# main.net
KiCad netlist of a schematic drawn in EAGLE
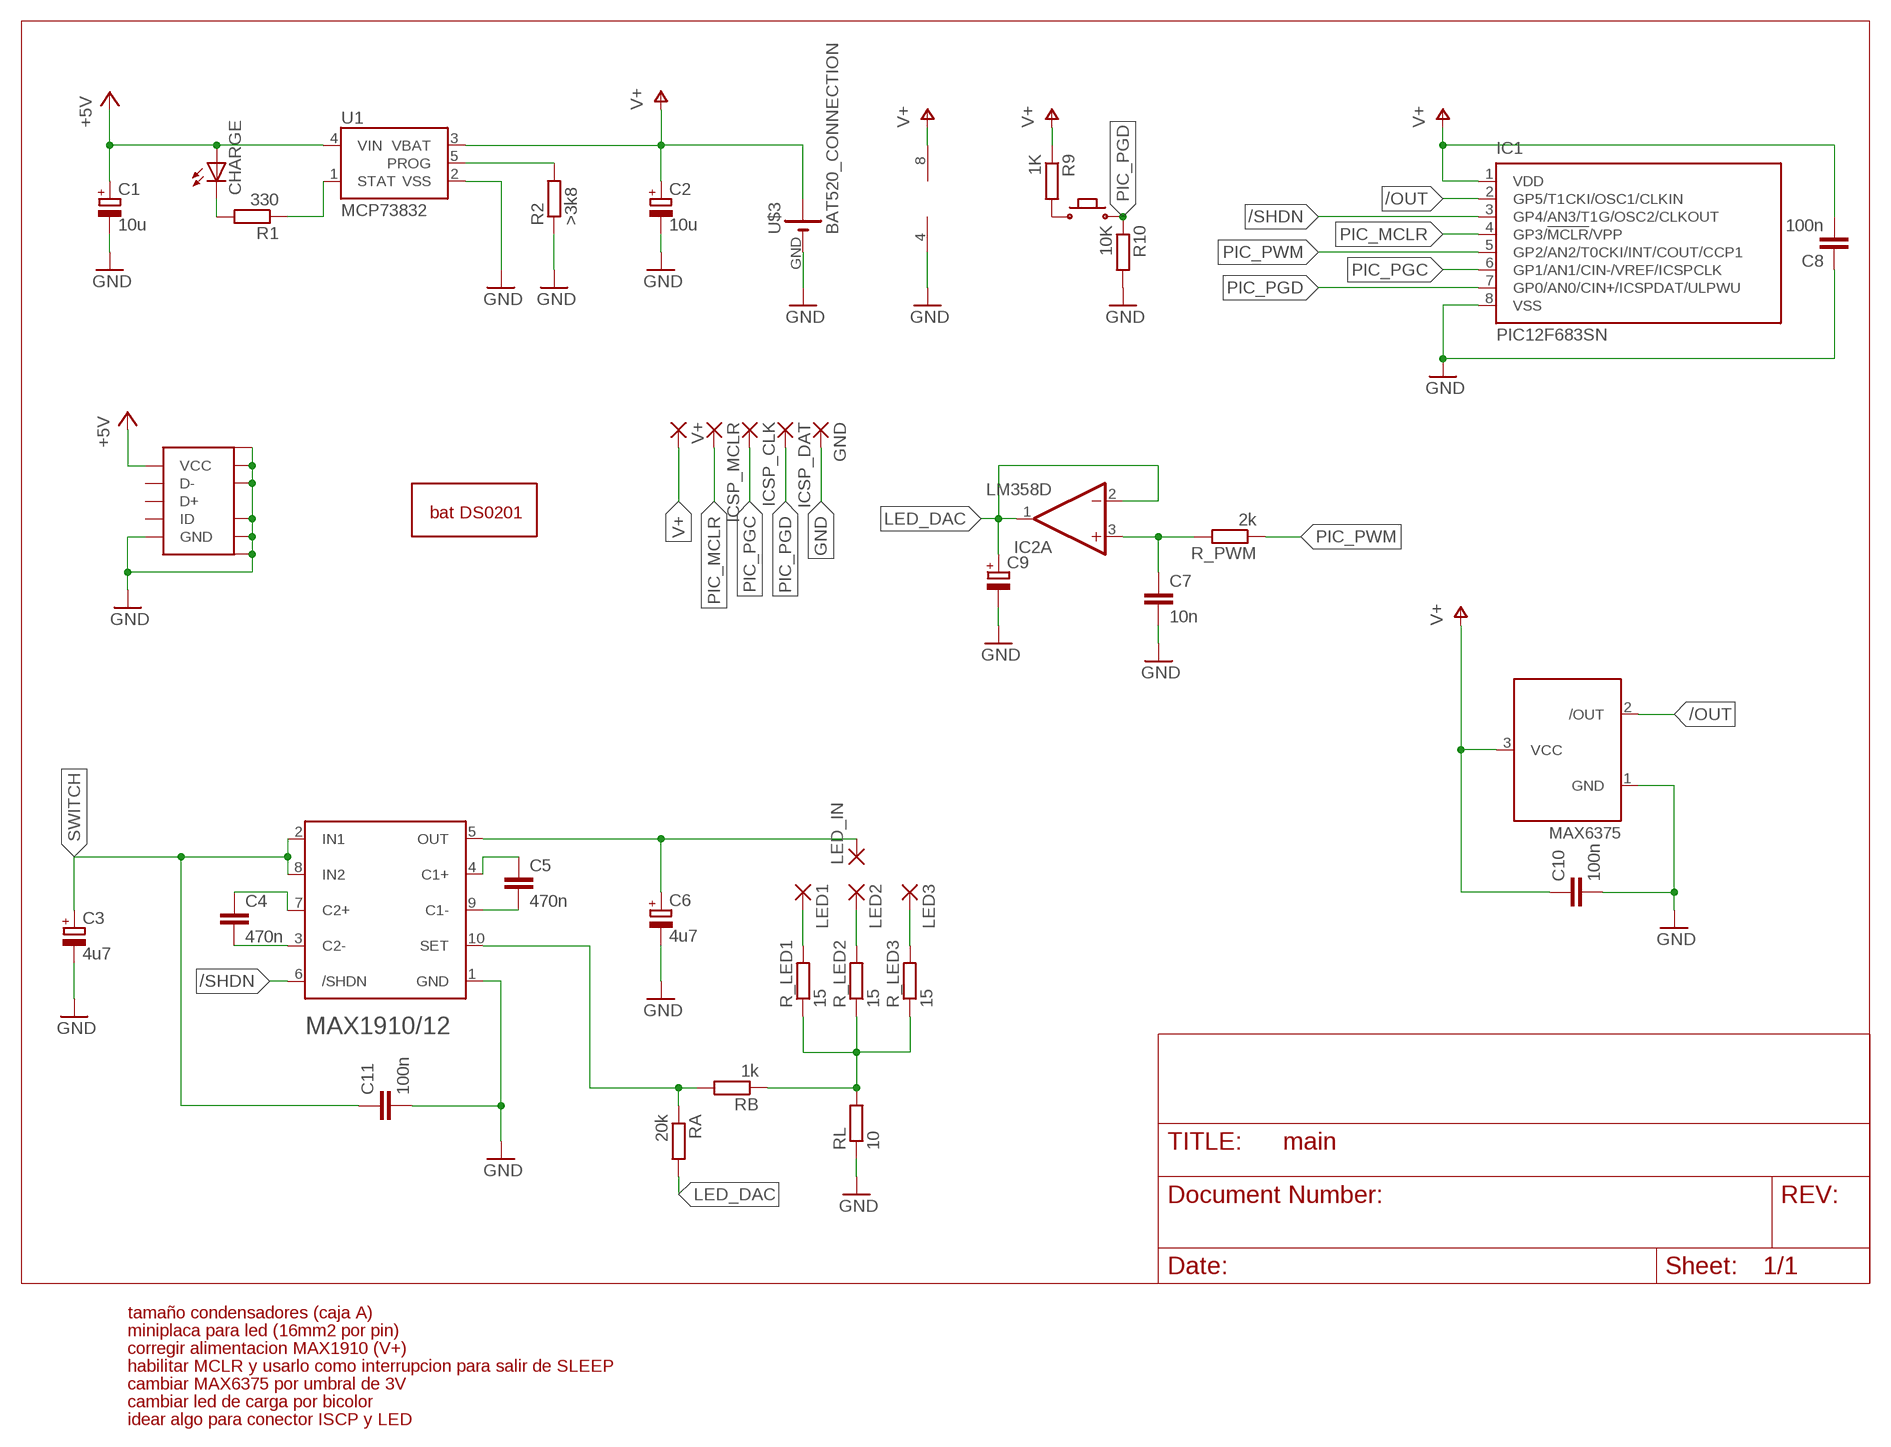
[diagram p0: schematic, sheet 1]

(export (version "E")
  (design (tool "Eeschema 10.0.6"))
  (components
    (comp (ref "C1")
      (value "10u")
      (footprint "eagle-import:SMC_A")
      (libsource (lib "eagle-import") (part "CPOL-EUSMCA"))
    )
    (comp (ref "C2")
      (value "10u")
      (footprint "eagle-import:SMC_A")
      (libsource (lib "eagle-import") (part "CPOL-EUSMCA"))
    )
    (comp (ref "C3")
      (value "4u7")
      (footprint "eagle-import:SMC_A")
      (libsource (lib "eagle-import") (part "CPOL-EUSMCA"))
    )
    (comp (ref "C4")
      (value "470n")
      (footprint "eagle-import:C1206")
      (libsource (lib "eagle-import") (part "C-EUC1206"))
    )
    (comp (ref "C5")
      (value "470n")
      (footprint "eagle-import:C1206")
      (libsource (lib "eagle-import") (part "C-EUC1206"))
    )
    (comp (ref "C6")
      (value "4u7")
      (footprint "eagle-import:SMC_A")
      (libsource (lib "eagle-import") (part "CPOL-EUSMCA"))
    )
    (comp (ref "C7")
      (value "10n")
      (footprint "eagle-import:C1206")
      (libsource (lib "eagle-import") (part "C-EUC1206"))
    )
    (comp (ref "C8")
      (value "100n")
      (footprint "eagle-import:C1206")
      (libsource (lib "eagle-import") (part "C-EUC1206"))
    )
    (comp (ref "C9")
      (value "CPOL-EUSMCA")
      (footprint "eagle-import:SMC_A")
      (libsource (lib "eagle-import") (part "CPOL-EUSMCA"))
    )
    (comp (ref "C10")
      (value "100n")
      (footprint "eagle-import:C1206")
      (libsource (lib "eagle-import") (part "C-EUC1206"))
    )
    (comp (ref "C11")
      (value "100n")
      (footprint "eagle-import:C1206")
      (libsource (lib "eagle-import") (part "C-EUC1206"))
    )
    (comp (ref "CHARGE")
      (value "LEDCHIPLED_1206")
      (footprint "eagle-import:CHIPLED_1206")
      (libsource (lib "eagle-import") (part "LEDCHIPLED_1206"))
    )
    (comp (ref "GND")
      (value "SMD5")
      (footprint "eagle-import:SMD2,54-5,08")
      (libsource (lib "eagle-import") (part "SMD5"))
    )
    (comp (ref "IC1")
      (value "PIC12F683SN")
      (footprint "eagle-import:SO-08")
      (fields (field (name "MF") "MICROCHIP") (field (name "MPN") "PIC12F683-I/SN"))
      (libsource (lib "eagle-import") (part "PIC12F683SN"))
    )
    (comp (ref "IC2")
      (value "LM358D")
      (footprint "eagle-import:SO08")
      (libsource (lib "eagle-import") (part "LM358D"))
    )
    (comp (ref "ICSP_CLK")
      (value "SMD5")
      (footprint "eagle-import:SMD2,54-5,08")
      (libsource (lib "eagle-import") (part "SMD5"))
    )
    (comp (ref "ICSP_DAT")
      (value "SMD5")
      (footprint "eagle-import:SMD2,54-5,08")
      (libsource (lib "eagle-import") (part "SMD5"))
    )
    (comp (ref "ICSP_MCLR")
      (value "SMD5")
      (footprint "eagle-import:SMD2,54-5,08")
      (libsource (lib "eagle-import") (part "SMD5"))
    )
    (comp (ref "LED1")
      (value "SMD5")
      (footprint "eagle-import:SMD2,54-5,08")
      (libsource (lib "eagle-import") (part "SMD5"))
    )
    (comp (ref "LED2")
      (value "SMD5")
      (footprint "eagle-import:SMD2,54-5,08")
      (libsource (lib "eagle-import") (part "SMD5"))
    )
    (comp (ref "LED3")
      (value "SMD5")
      (footprint "eagle-import:SMD2,54-5,08")
      (libsource (lib "eagle-import") (part "SMD5"))
    )
    (comp (ref "LED_IN")
      (value "SMD5")
      (footprint "eagle-import:SMD2,54-5,08")
      (libsource (lib "eagle-import") (part "SMD5"))
    )
    (comp (ref "R1")
      (value "330")
      (footprint "eagle-import:R1206")
      (libsource (lib "eagle-import") (part "R-EU_R1206"))
    )
    (comp (ref "R2")
      (value ">3k8")
      (footprint "eagle-import:R1206")
      (libsource (lib "eagle-import") (part "R-EU_R1206"))
    )
    (comp (ref "R9")
      (value "1K")
      (footprint "eagle-import:R1206")
      (libsource (lib "eagle-import") (part "R-EU_R1206"))
    )
    (comp (ref "R10")
      (value "10K")
      (footprint "eagle-import:R1206")
      (libsource (lib "eagle-import") (part "R-EU_R1206"))
    )
    (comp (ref "RA")
      (value "20k")
      (footprint "eagle-import:R1206")
      (libsource (lib "eagle-import") (part "R-EU_R1206"))
    )
    (comp (ref "RB")
      (value "1k")
      (footprint "eagle-import:R1206")
      (libsource (lib "eagle-import") (part "R-EU_R1206"))
    )
    (comp (ref "RL")
      (value "10")
      (footprint "eagle-import:R1206")
      (libsource (lib "eagle-import") (part "R-EU_R1206"))
    )
    (comp (ref "R_LED1")
      (value "15")
      (footprint "eagle-import:R1206")
      (libsource (lib "eagle-import") (part "R-EU_R1206"))
    )
    (comp (ref "R_LED2")
      (value "15")
      (footprint "eagle-import:R1206")
      (libsource (lib "eagle-import") (part "R-EU_R1206"))
    )
    (comp (ref "R_LED3")
      (value "15")
      (footprint "eagle-import:R1206")
      (libsource (lib "eagle-import") (part "R-EU_R1206"))
    )
    (comp (ref "R_PWM")
      (value "2k")
      (footprint "eagle-import:R1206")
      (libsource (lib "eagle-import") (part "R-EU_R1206"))
    )
    (comp (ref "U$1")
      (value "MAX1910/12")
      (footprint "eagle-import:UMAX_USOP_10L")
      (libsource (lib "eagle-import") (part "MAX1910/12"))
    )
    (comp (ref "U$2")
      (value "MAX6375")
      (footprint "eagle-import:SC70-3-W")
      (libsource (lib "eagle-import") (part "MAX6375"))
    )
    (comp (ref "U$3")
      (value "BAT520_CONNECTION")
      (footprint "eagle-import:BAT520_CONN_SMD")
      (libsource (lib "eagle-import") (part "BAT520_CONNECTION"))
    )
    (comp (ref "U$4")
      (value "BAT_DS0201_PACKAGE")
      (footprint "eagle-import:BAT_DS0201")
      (libsource (lib "eagle-import") (part "BAT_DS0201_PACKAGE"))
    )
    (comp (ref "U$5")
      (value "MICRO_USB_B")
      (footprint "eagle-import:MICRO_USB_B")
      (libsource (lib "eagle-import") (part "MICRO_USB_B"))
    )
    (comp (ref "U$6")
      (value "MICROBUTTONE-MERCHAN")
      (footprint "eagle-import:MICROBUTTON_2")
      (libsource (lib "eagle-import") (part "MICROBUTTONE-MERCHAN"))
    )
    (comp (ref "U1")
      (value "MCP73832")
      (footprint "eagle-import:SOT23-5")
      (libsource (lib "eagle-import") (part "MCP73832"))
    )
    (comp (ref "V+")
      (value "SMD5")
      (footprint "eagle-import:SMD2,54-5,08")
      (libsource (lib "eagle-import") (part "SMD5"))
    )
  )
  (nets
    (net (code "1") (name "+5V") (class "Default")
      (node (ref "C1") (pin "+") (pinfunction "+_+") (pintype "passive"))
      (node (ref "CHARGE") (pin "A") (pinfunction "A_A") (pintype "passive"))
      (node (ref "U$5") (pin "1") (pinfunction "VCC_1") (pintype "power_in"))
      (node (ref "U1") (pin "4") (pinfunction "VIN_4") (pintype "power_in"))
    )
    (net (code "2") (name "GND") (class "Default")
      (node (ref "C1") (pin "-") (pinfunction "-_-") (pintype "passive"))
      (node (ref "C10") (pin "2") (pinfunction "2_2") (pintype "passive"))
      (node (ref "C11") (pin "2") (pinfunction "2_2") (pintype "passive"))
      (node (ref "C2") (pin "-") (pinfunction "-_-") (pintype "passive"))
      (node (ref "C3") (pin "-") (pinfunction "-_-") (pintype "passive"))
      (node (ref "C6") (pin "-") (pinfunction "-_-") (pintype "passive"))
      (node (ref "C7") (pin "2") (pinfunction "2_2") (pintype "passive"))
      (node (ref "C8") (pin "1") (pinfunction "1_1") (pintype "passive"))
      (node (ref "C9") (pin "-") (pinfunction "-_-") (pintype "passive"))
      (node (ref "GND") (pin "1") (pinfunction "P_1") (pintype "passive"))
      (node (ref "IC1") (pin "8") (pinfunction "VSS_8") (pintype "power_in"))
      (node (ref "IC2") (pin "4") (pinfunction "V-_4") (pintype "power_in"))
      (node (ref "R10") (pin "2") (pinfunction "2_2") (pintype "passive"))
      (node (ref "R2") (pin "1") (pinfunction "1_1") (pintype "passive"))
      (node (ref "RL") (pin "1") (pinfunction "1_1") (pintype "passive"))
      (node (ref "U$1") (pin "1") (pinfunction "GND_1") (pintype "power_in"))
      (node (ref "U$2") (pin "1") (pinfunction "GND_1") (pintype "power_in"))
      (node (ref "U$3") (pin "GND") (pinfunction "-_GND") (pintype "passive"))
      (node (ref "U$5") (pin "5") (pinfunction "GND_5") (pintype "power_in"))
      (node (ref "U$5") (pin "GND1") (pinfunction "GND_GND1") (pintype "power_in"))
      (node (ref "U$5") (pin "GND2") (pinfunction "GND_GND2") (pintype "power_in"))
      (node (ref "U$5") (pin "GND3") (pinfunction "GND_GND3") (pintype "power_in"))
      (node (ref "U$5") (pin "GND4") (pinfunction "GND_GND4") (pintype "power_in"))
      (node (ref "U$5") (pin "GND5") (pinfunction "GND_GND5") (pintype "power_in"))
      (node (ref "U$5") (pin "GND6") (pinfunction "GND_GND6") (pintype "power_in"))
      (node (ref "U1") (pin "2") (pinfunction "VSS_2") (pintype "power_in"))
    )
    (net (code "3") (name "LED_DAC") (class "Default")
      (node (ref "C9") (pin "+") (pinfunction "+_+") (pintype "passive"))
      (node (ref "IC2") (pin "1") (pinfunction "OUT_1") (pintype "output"))
      (node (ref "IC2") (pin "2") (pinfunction "-IN_2") (pintype "input"))
      (node (ref "RA") (pin "2") (pinfunction "2_2") (pintype "passive"))
    )
    (net (code "4") (name "Net-(CHARGE-PadC)") (class "Default")
      (node (ref "CHARGE") (pin "C") (pinfunction "C_C") (pintype "passive"))
      (node (ref "R1") (pin "2") (pinfunction "2_2") (pintype "passive"))
    )
    (net (code "5") (name "Net-(IC2A-+IN)") (class "Default")
      (node (ref "C7") (pin "1") (pinfunction "1_1") (pintype "passive"))
      (node (ref "IC2") (pin "3") (pinfunction "+IN_3") (pintype "input"))
      (node (ref "R_PWM") (pin "2") (pinfunction "2_2") (pintype "passive"))
    )
    (net (code "6") (name "Net-(LED1-P)") (class "Default")
      (node (ref "LED1") (pin "1") (pinfunction "P_1") (pintype "passive"))
      (node (ref "R_LED1") (pin "2") (pinfunction "2_2") (pintype "passive"))
    )
    (net (code "7") (name "Net-(LED2-P)") (class "Default")
      (node (ref "LED2") (pin "1") (pinfunction "P_1") (pintype "passive"))
      (node (ref "R_LED2") (pin "2") (pinfunction "2_2") (pintype "passive"))
    )
    (net (code "8") (name "Net-(LED3-P)") (class "Default")
      (node (ref "LED3") (pin "1") (pinfunction "P_1") (pintype "passive"))
      (node (ref "R_LED3") (pin "2") (pinfunction "2_2") (pintype "passive"))
    )
    (net (code "9") (name "Net-(LED_IN-P)") (class "Default")
      (node (ref "C6") (pin "+") (pinfunction "+_+") (pintype "passive"))
      (node (ref "LED_IN") (pin "1") (pinfunction "P_1") (pintype "passive"))
      (node (ref "U$1") (pin "5") (pinfunction "OUT_5") (pintype "output"))
    )
    (net (code "10") (name "Net-(R9-Pad2)") (class "Default")
      (node (ref "R9") (pin "2") (pinfunction "2_2") (pintype "passive"))
      (node (ref "U$6") (pin "P$1") (pinfunction "P$1_P$1") (pintype "bidirectional"))
    )
    (net (code "11") (name "Net-(RB-Pad1)") (class "Default")
      (node (ref "RB") (pin "1") (pinfunction "1_1") (pintype "passive"))
      (node (ref "RL") (pin "2") (pinfunction "2_2") (pintype "passive"))
      (node (ref "R_LED1") (pin "1") (pinfunction "1_1") (pintype "passive"))
      (node (ref "R_LED2") (pin "1") (pinfunction "1_1") (pintype "passive"))
      (node (ref "R_LED3") (pin "1") (pinfunction "1_1") (pintype "passive"))
    )
    (net (code "12") (name "Net-(U$1-C1+)") (class "Default")
      (node (ref "C5") (pin "1") (pinfunction "1_1") (pintype "passive"))
      (node (ref "U$1") (pin "4") (pinfunction "C1+_4") (pintype "bidirectional"))
    )
    (net (code "13") (name "Net-(U$1-C1-)") (class "Default")
      (node (ref "C5") (pin "2") (pinfunction "2_2") (pintype "passive"))
      (node (ref "U$1") (pin "9") (pinfunction "C1-_9") (pintype "bidirectional"))
    )
    (net (code "14") (name "Net-(U$1-C2+)") (class "Default")
      (node (ref "C4") (pin "1") (pinfunction "1_1") (pintype "passive"))
      (node (ref "U$1") (pin "7") (pinfunction "C2+_7") (pintype "bidirectional"))
    )
    (net (code "15") (name "Net-(U$1-C2-)") (class "Default")
      (node (ref "C4") (pin "2") (pinfunction "2_2") (pintype "passive"))
      (node (ref "U$1") (pin "3") (pinfunction "C2-_3") (pintype "bidirectional"))
    )
    (net (code "16") (name "Net-(U$1-SET)") (class "Default")
      (node (ref "RA") (pin "1") (pinfunction "1_1") (pintype "passive"))
      (node (ref "RB") (pin "2") (pinfunction "2_2") (pintype "passive"))
      (node (ref "U$1") (pin "10") (pinfunction "SET_10") (pintype "input"))
    )
    (net (code "17") (name "Net-(U1-PROG)") (class "Default")
      (node (ref "R2") (pin "2") (pinfunction "2_2") (pintype "passive"))
      (node (ref "U1") (pin "5") (pinfunction "PROG_5") (pintype "input"))
    )
    (net (code "18") (name "Net-(U1-STAT)") (class "Default")
      (node (ref "R1") (pin "1") (pinfunction "1_1") (pintype "passive"))
      (node (ref "U1") (pin "1") (pinfunction "STAT_1") (pintype "output"))
    )
    (net (code "19") (name "PIC_MCLR") (class "Default")
      (node (ref "IC1") (pin "4") (pinfunction "GP3/~{MCLR}/VPP_4") (pintype "bidirectional"))
      (node (ref "ICSP_MCLR") (pin "1") (pinfunction "P_1") (pintype "passive"))
    )
    (net (code "20") (name "PIC_PGC") (class "Default")
      (node (ref "IC1") (pin "6") (pinfunction "GP1/AN1/CIN-/VREF/ICSPCLK_6") (pintype "bidirectional"))
      (node (ref "ICSP_CLK") (pin "1") (pinfunction "P_1") (pintype "passive"))
    )
    (net (code "21") (name "PIC_PGD") (class "Default")
      (node (ref "IC1") (pin "7") (pinfunction "GP0/AN0/CIN+/ICSPDAT/ULPWU_7") (pintype "bidirectional"))
      (node (ref "ICSP_DAT") (pin "1") (pinfunction "P_1") (pintype "passive"))
      (node (ref "R10") (pin "1") (pinfunction "1_1") (pintype "passive"))
      (node (ref "U$6") (pin "P$2") (pinfunction "P$2_P$2") (pintype "bidirectional"))
    )
    (net (code "22") (name "PIC_PWM") (class "Default")
      (node (ref "IC1") (pin "5") (pinfunction "GP2/AN2/T0CKI/INT/COUT/CCP1_5") (pintype "bidirectional"))
      (node (ref "R_PWM") (pin "1") (pinfunction "1_1") (pintype "passive"))
    )
    (net (code "23") (name "SWITCH") (class "Default")
      (node (ref "C11") (pin "1") (pinfunction "1_1") (pintype "passive"))
      (node (ref "C3") (pin "+") (pinfunction "+_+") (pintype "passive"))
      (node (ref "U$1") (pin "2") (pinfunction "IN1_2") (pintype "power_in"))
      (node (ref "U$1") (pin "8") (pinfunction "IN2_8") (pintype "power_in"))
    )
    (net (code "24") (name "V+") (class "Default")
      (node (ref "C10") (pin "1") (pinfunction "1_1") (pintype "passive"))
      (node (ref "C2") (pin "+") (pinfunction "+_+") (pintype "passive"))
      (node (ref "C8") (pin "2") (pinfunction "2_2") (pintype "passive"))
      (node (ref "IC1") (pin "1") (pinfunction "VDD_1") (pintype "power_in"))
      (node (ref "IC2") (pin "8") (pinfunction "V+_8") (pintype "power_in"))
      (node (ref "R9") (pin "1") (pinfunction "1_1") (pintype "passive"))
      (node (ref "U$2") (pin "3") (pinfunction "VCC_3") (pintype "power_in"))
      (node (ref "U$3") (pin "VCC") (pinfunction "+_VCC") (pintype "passive"))
      (node (ref "U1") (pin "3") (pinfunction "VBAT_3") (pintype "power_in"))
      (node (ref "V+") (pin "1") (pinfunction "P_1") (pintype "passive"))
    )
    (net (code "25") (name "unconnected-(U$5-D+-Pad3)") (class "Default")
      (node (ref "U$5") (pin "3") (pinfunction "D+_3") (pintype "bidirectional"))
    )
    (net (code "26") (name "unconnected-(U$5-D--Pad2)") (class "Default")
      (node (ref "U$5") (pin "2") (pinfunction "D-_2") (pintype "bidirectional"))
    )
    (net (code "27") (name "unconnected-(U$5-ID-Pad4)") (class "Default")
      (node (ref "U$5") (pin "4") (pinfunction "ID_4") (pintype "bidirectional"))
    )
    (net (code "28") (name "{slash}OUT") (class "Default")
      (node (ref "IC1") (pin "2") (pinfunction "GP5/T1CKI/OSC1/CLKIN_2") (pintype "bidirectional"))
      (node (ref "U$2") (pin "2") (pinfunction "/OUT_2") (pintype "output"))
    )
    (net (code "29") (name "{slash}SHDN") (class "Default")
      (node (ref "IC1") (pin "3") (pinfunction "GP4/AN3/T1G/OSC2/CLKOUT_3") (pintype "bidirectional"))
      (node (ref "U$1") (pin "6") (pinfunction "/SHDN_6") (pintype "bidirectional"))
    )
  )
)
